# untitled.net
KiCad netlist of a schematic drawn in EAGLE
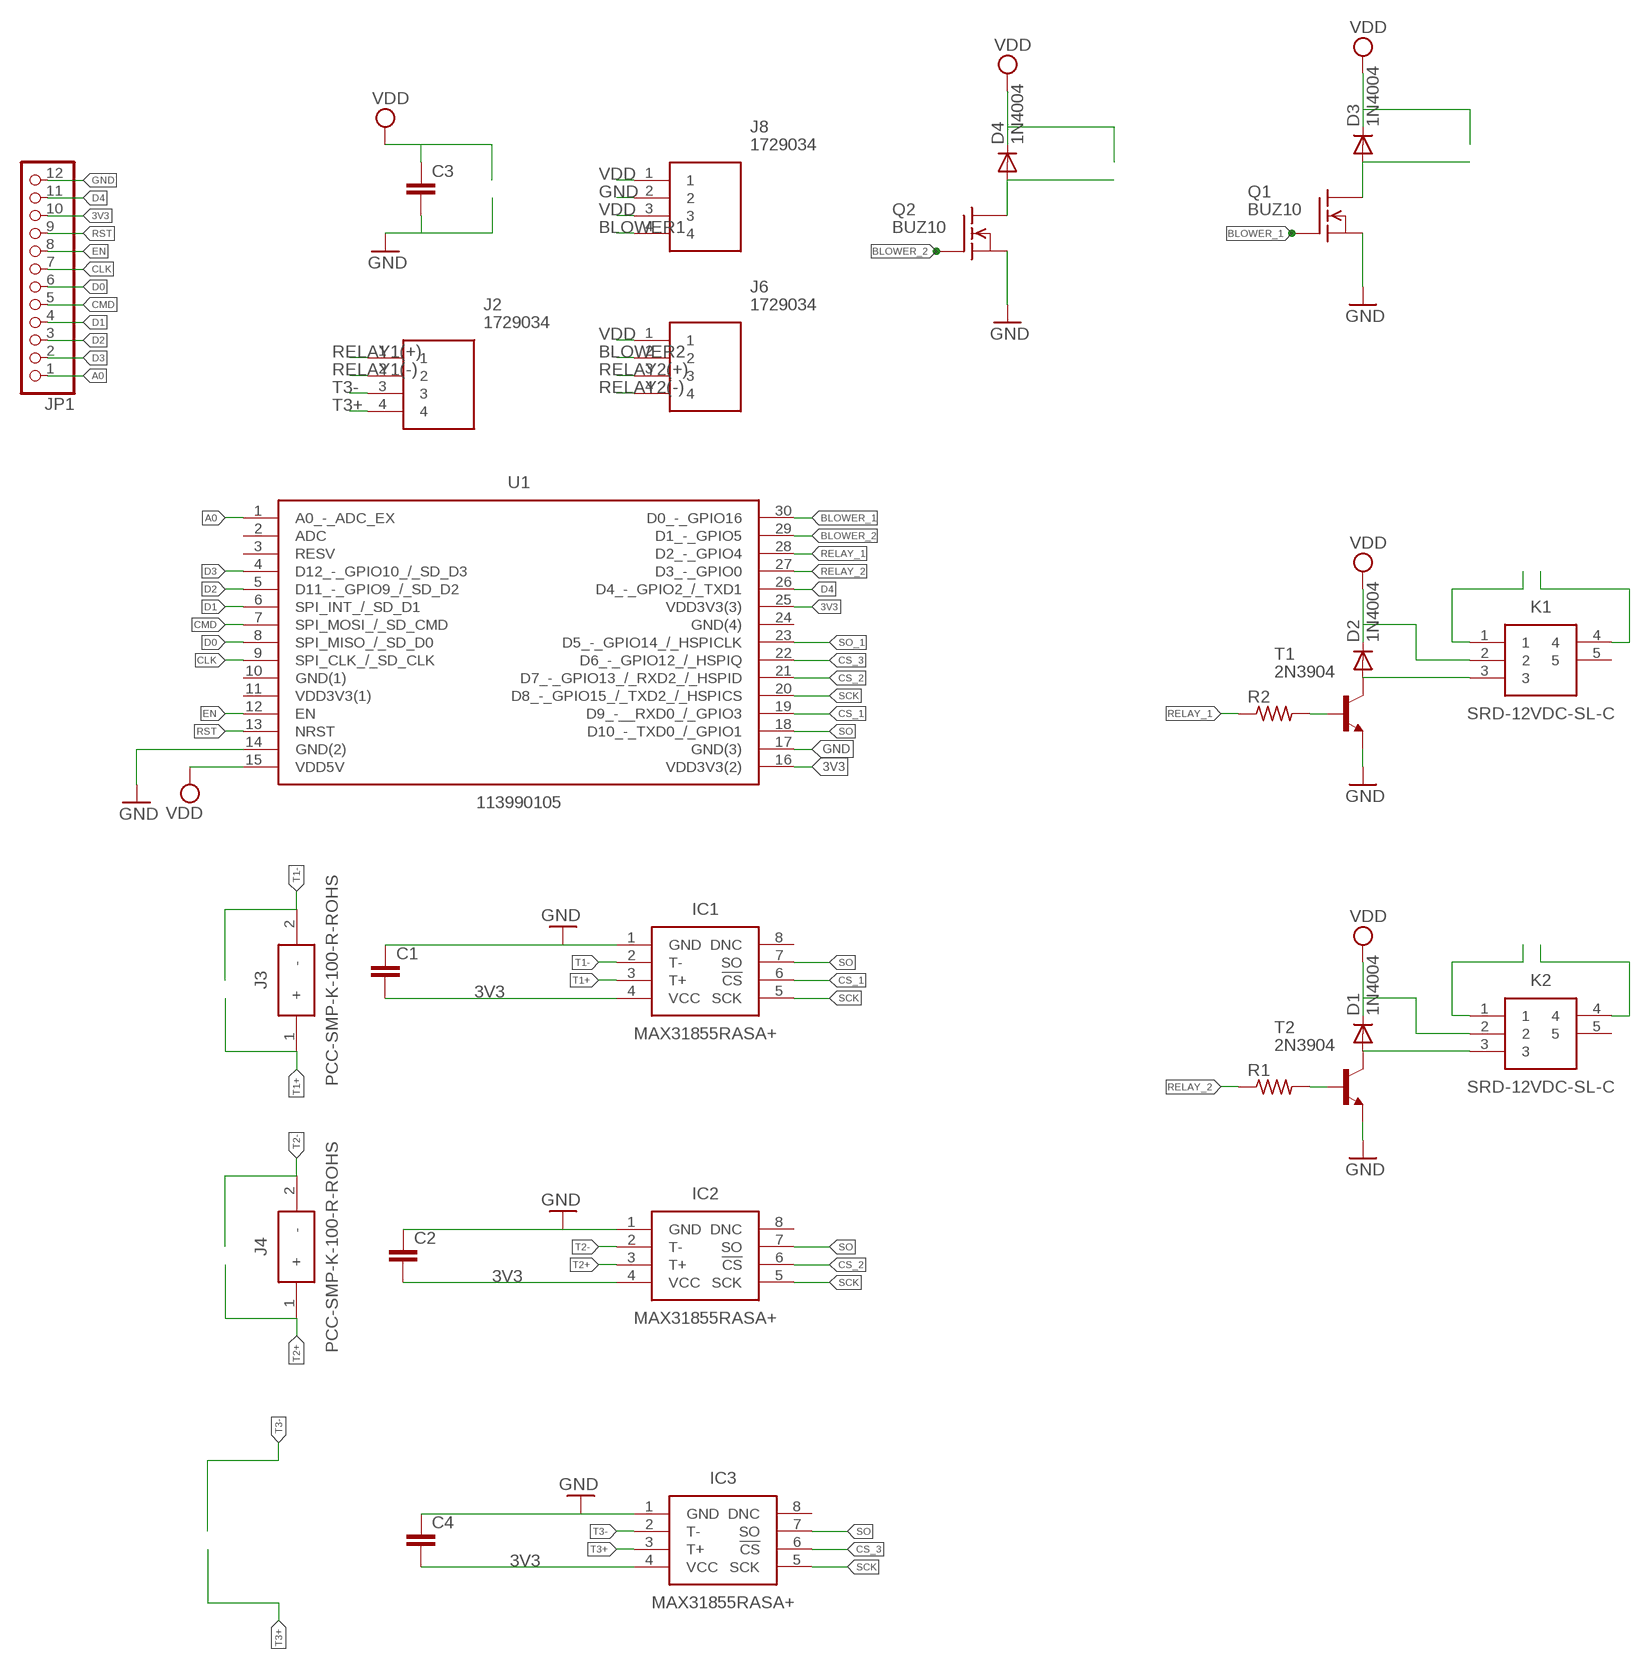
[diagram p0: schematic, sheet 1]

(export (version "E")
  (design (tool "Eeschema 10.0.6"))
  (components
    (comp (ref "C1")
      (value "C2,5-3")
      (footprint "eagle-import:C2.5-3")
      (libsource (lib "eagle-import") (part "C2,5-3"))
    )
    (comp (ref "C2")
      (value "C2,5-3")
      (footprint "eagle-import:C2.5-3")
      (libsource (lib "eagle-import") (part "C2,5-3"))
    )
    (comp (ref "C3")
      (value "C2.5/4")
      (footprint "eagle-import:C2.5-4")
      (libsource (lib "eagle-import") (part "C2.5/4"))
    )
    (comp (ref "C4")
      (value "C2,5-3")
      (footprint "eagle-import:C2.5-3")
      (libsource (lib "eagle-import") (part "C2,5-3"))
    )
    (comp (ref "D1")
      (value "1N4004")
      (footprint "eagle-import:DO41-10")
      (libsource (lib "eagle-import") (part "1N4004"))
    )
    (comp (ref "D2")
      (value "1N4004")
      (footprint "eagle-import:DO41-10")
      (libsource (lib "eagle-import") (part "1N4004"))
    )
    (comp (ref "D3")
      (value "1N4004")
      (footprint "eagle-import:DO41-10")
      (libsource (lib "eagle-import") (part "1N4004"))
    )
    (comp (ref "D4")
      (value "1N4004")
      (footprint "eagle-import:DO41-10")
      (libsource (lib "eagle-import") (part "1N4004"))
    )
    (comp (ref "IC1")
      (value "MAX31855RASA+")
      (footprint "eagle-import:SOIC127P600X175-8N")
      (fields (field (name "RS_PART_NUMBER") "7833891P"))
      (libsource (lib "eagle-import") (part "MAX31855RASA+"))
    )
    (comp (ref "IC2")
      (value "MAX31855RASA+")
      (footprint "eagle-import:SOIC127P600X175-8N")
      (fields (field (name "RS_PART_NUMBER") "7833891P"))
      (libsource (lib "eagle-import") (part "MAX31855RASA+"))
    )
    (comp (ref "IC3")
      (value "MAX31855RASA+")
      (footprint "eagle-import:SOIC127P600X175-8N")
      (fields (field (name "RS_PART_NUMBER") "7833891P"))
      (libsource (lib "eagle-import") (part "MAX31855RASA+"))
    )
    (comp (ref "J2")
      (value "1729034")
      (footprint "eagle-import:SHDR4W110P0X500_1X4_2000X810X1")
      (fields (field (name "RS_PART_NUMBER") "8020620"))
      (libsource (lib "eagle-import") (part "1729034"))
    )
    (comp (ref "J3")
      (value "PCC-SMP-K-100-R-ROHS")
      (footprint "eagle-import:PCC-SMP")
      (libsource (lib "eagle-import") (part "PCC-SMP-K-100-R-ROHS"))
    )
    (comp (ref "J4")
      (value "PCC-SMP-K-100-R-ROHS")
      (footprint "eagle-import:PCC-SMP")
      (libsource (lib "eagle-import") (part "PCC-SMP-K-100-R-ROHS"))
    )
    (comp (ref "J6")
      (value "1729034")
      (footprint "eagle-import:SHDR4W110P0X500_1X4_2000X810X1")
      (fields (field (name "RS_PART_NUMBER") "8020620"))
      (libsource (lib "eagle-import") (part "1729034"))
    )
    (comp (ref "J8")
      (value "1729034")
      (footprint "eagle-import:SHDR4W110P0X500_1X4_2000X810X1")
      (fields (field (name "RS_PART_NUMBER") "8020620"))
      (libsource (lib "eagle-import") (part "1729034"))
    )
    (comp (ref "JP1")
      (value "PINHD-1X12")
      (footprint "eagle-import:1X12")
      (libsource (lib "eagle-import") (part "PINHD-1X12"))
    )
    (comp (ref "K1")
      (value "SRD-12VDC-SL-C")
      (footprint "eagle-import:SRD")
      (libsource (lib "eagle-import") (part "SRD-12VDC-SL-C"))
    )
    (comp (ref "K2")
      (value "SRD-12VDC-SL-C")
      (footprint "eagle-import:SRD")
      (libsource (lib "eagle-import") (part "SRD-12VDC-SL-C"))
    )
    (comp (ref "Q1")
      (value "BUZ10")
      (footprint "eagle-import:TO220")
      (libsource (lib "eagle-import") (part "BUZ10"))
    )
    (comp (ref "Q2")
      (value "BUZ10")
      (footprint "eagle-import:TO220")
      (libsource (lib "eagle-import") (part "BUZ10"))
    )
    (comp (ref "R1")
      (value "R-US_0207/7")
      (footprint "eagle-import:0207_7")
      (libsource (lib "eagle-import") (part "R-US_0207/7"))
    )
    (comp (ref "R2")
      (value "R-US_0207/7")
      (footprint "eagle-import:0207_7")
      (libsource (lib "eagle-import") (part "R-US_0207/7"))
    )
    (comp (ref "T1")
      (value "2N3904")
      (footprint "eagle-import:TO92")
      (libsource (lib "eagle-import") (part "2N3904"))
    )
    (comp (ref "T2")
      (value "2N3904")
      (footprint "eagle-import:TO92")
      (libsource (lib "eagle-import") (part "2N3904"))
    )
    (comp (ref "U1")
      (value "113990105")
      (footprint "eagle-import:DIP2286W64P254L4826H735Q30N")
      (libsource (lib "eagle-import") (part "113990105"))
    )
  )
  (nets
    (net (code "1") (name "/BLOWER1") (class "Default")
      (node (ref "D3") (pin "A") (pinfunction "A_A") (pintype "passive"))
      (node (ref "J8") (pin "4") (pinfunction "4_4") (pintype "bidirectional"))
      (node (ref "Q1") (pin "2") (pinfunction "D_2") (pintype "passive"))
    )
    (net (code "2") (name "/BLOWER2") (class "Default")
      (node (ref "D4") (pin "A") (pinfunction "A_A") (pintype "passive"))
      (node (ref "J6") (pin "2") (pinfunction "2_2") (pintype "bidirectional"))
      (node (ref "Q2") (pin "2") (pinfunction "D_2") (pintype "passive"))
    )
    (net (code "3") (name "/GND(1)") (class "Default")
      (node (ref "U1") (pin "10") (pinfunction "GND(1)_10") (pintype "power_in"))
    )
    (net (code "4") (name "/GND(4)") (class "Default")
      (node (ref "U1") (pin "24") (pinfunction "GND(4)_24") (pintype "power_in"))
    )
    (net (code "5") (name "/RELAY1(+)") (class "Default")
      (node (ref "J2") (pin "1") (pinfunction "1_1") (pintype "bidirectional"))
      (node (ref "K1") (pin "4") (pinfunction "4_4") (pintype "passive"))
    )
    (net (code "6") (name "/RELAY1(-)") (class "Default")
      (node (ref "J2") (pin "2") (pinfunction "2_2") (pintype "bidirectional"))
      (node (ref "K1") (pin "1") (pinfunction "1_1") (pintype "passive"))
    )
    (net (code "7") (name "/RELAY2(+)") (class "Default")
      (node (ref "J6") (pin "3") (pinfunction "3_3") (pintype "bidirectional"))
      (node (ref "K2") (pin "4") (pinfunction "4_4") (pintype "passive"))
    )
    (net (code "8") (name "/RELAY2(-)") (class "Default")
      (node (ref "J6") (pin "4") (pinfunction "4_4") (pintype "bidirectional"))
      (node (ref "K2") (pin "1") (pinfunction "1_1") (pintype "passive"))
    )
    (net (code "9") (name "/VDD3V3(1)") (class "Default")
      (node (ref "U1") (pin "11") (pinfunction "VDD3V3(1)_11") (pintype "power_in"))
    )
    (net (code "10") (name "3V3") (class "Default")
      (node (ref "C1") (pin "2") (pinfunction "2_2") (pintype "passive"))
      (node (ref "C2") (pin "2") (pinfunction "2_2") (pintype "passive"))
      (node (ref "C4") (pin "2") (pinfunction "2_2") (pintype "passive"))
      (node (ref "IC1") (pin "4") (pinfunction "VCC_4") (pintype "power_in"))
      (node (ref "IC2") (pin "4") (pinfunction "VCC_4") (pintype "power_in"))
      (node (ref "IC3") (pin "4") (pinfunction "VCC_4") (pintype "power_in"))
      (node (ref "JP1") (pin "10") (pinfunction "10_10") (pintype "passive"))
      (node (ref "U1") (pin "16") (pinfunction "VDD3V3(2)_16") (pintype "power_in"))
      (node (ref "U1") (pin "25") (pinfunction "VDD3V3(3)_25") (pintype "power_in"))
    )
    (net (code "11") (name "A0") (class "Default")
      (node (ref "JP1") (pin "1") (pinfunction "1_1") (pintype "passive"))
      (node (ref "U1") (pin "1") (pinfunction "A0_-_ADC_EX_1") (pintype "bidirectional"))
    )
    (net (code "12") (name "BLOWER_1") (class "Default")
      (node (ref "Q1") (pin "1") (pinfunction "G_1") (pintype "passive"))
      (node (ref "U1") (pin "30") (pinfunction "D0_-_GPIO16_30") (pintype "bidirectional"))
    )
    (net (code "13") (name "BLOWER_2") (class "Default")
      (node (ref "Q2") (pin "1") (pinfunction "G_1") (pintype "passive"))
      (node (ref "U1") (pin "29") (pinfunction "D1_-_GPIO5_29") (pintype "bidirectional"))
    )
    (net (code "14") (name "CLK") (class "Default")
      (node (ref "JP1") (pin "7") (pinfunction "7_7") (pintype "passive"))
      (node (ref "U1") (pin "9") (pinfunction "SPI_CLK_/_SD_CLK_9") (pintype "bidirectional"))
    )
    (net (code "15") (name "CMD") (class "Default")
      (node (ref "JP1") (pin "5") (pinfunction "5_5") (pintype "passive"))
      (node (ref "U1") (pin "7") (pinfunction "SPI_MOSI_/_SD_CMD_7") (pintype "bidirectional"))
    )
    (net (code "16") (name "CS_1") (class "Default")
      (node (ref "IC1") (pin "6") (pinfunction "~{CS}_6") (pintype "input"))
      (node (ref "U1") (pin "19") (pinfunction "D9_-__RXD0_/_GPIO3_19") (pintype "bidirectional"))
    )
    (net (code "17") (name "CS_2") (class "Default")
      (node (ref "IC2") (pin "6") (pinfunction "~{CS}_6") (pintype "input"))
      (node (ref "U1") (pin "21") (pinfunction "D7_-_GPIO13_/_RXD2_/_HSPID_21") (pintype "bidirectional"))
    )
    (net (code "18") (name "CS_3") (class "Default")
      (node (ref "IC3") (pin "6") (pinfunction "~{CS}_6") (pintype "input"))
      (node (ref "U1") (pin "22") (pinfunction "D6_-_GPIO12_/_HSPIQ_22") (pintype "bidirectional"))
    )
    (net (code "19") (name "D0") (class "Default")
      (node (ref "JP1") (pin "6") (pinfunction "6_6") (pintype "passive"))
      (node (ref "U1") (pin "8") (pinfunction "SPI_MISO_/_SD_D0_8") (pintype "bidirectional"))
    )
    (net (code "20") (name "D1") (class "Default")
      (node (ref "JP1") (pin "4") (pinfunction "4_4") (pintype "passive"))
      (node (ref "U1") (pin "6") (pinfunction "SPI_INT_/_SD_D1_6") (pintype "bidirectional"))
    )
    (net (code "21") (name "D2") (class "Default")
      (node (ref "JP1") (pin "3") (pinfunction "3_3") (pintype "passive"))
      (node (ref "U1") (pin "5") (pinfunction "D11_-_GPIO9_/_SD_D2_5") (pintype "bidirectional"))
    )
    (net (code "22") (name "D3") (class "Default")
      (node (ref "JP1") (pin "2") (pinfunction "2_2") (pintype "passive"))
      (node (ref "U1") (pin "4") (pinfunction "D12_-_GPIO10_/_SD_D3_4") (pintype "bidirectional"))
    )
    (net (code "23") (name "D4") (class "Default")
      (node (ref "JP1") (pin "11") (pinfunction "11_11") (pintype "passive"))
      (node (ref "U1") (pin "26") (pinfunction "D4_-_GPIO2_/_TXD1_26") (pintype "bidirectional"))
    )
    (net (code "24") (name "EN") (class "Default")
      (node (ref "JP1") (pin "8") (pinfunction "8_8") (pintype "passive"))
      (node (ref "U1") (pin "12") (pinfunction "EN_12") (pintype "input"))
    )
    (net (code "25") (name "GND") (class "Default")
      (node (ref "C1") (pin "1") (pinfunction "1_1") (pintype "passive"))
      (node (ref "C2") (pin "1") (pinfunction "1_1") (pintype "passive"))
      (node (ref "C3") (pin "2") (pinfunction "2_2") (pintype "passive"))
      (node (ref "C4") (pin "1") (pinfunction "1_1") (pintype "passive"))
      (node (ref "IC1") (pin "1") (pinfunction "GND_1") (pintype "power_in"))
      (node (ref "IC2") (pin "1") (pinfunction "GND_1") (pintype "power_in"))
      (node (ref "IC3") (pin "1") (pinfunction "GND_1") (pintype "power_in"))
      (node (ref "J8") (pin "2") (pinfunction "2_2") (pintype "bidirectional"))
      (node (ref "JP1") (pin "12") (pinfunction "12_12") (pintype "passive"))
      (node (ref "Q1") (pin "3") (pinfunction "S_3") (pintype "passive"))
      (node (ref "Q2") (pin "3") (pinfunction "S_3") (pintype "passive"))
      (node (ref "T1") (pin "3") (pinfunction "E_3") (pintype "passive"))
      (node (ref "T2") (pin "3") (pinfunction "E_3") (pintype "passive"))
      (node (ref "U1") (pin "14") (pinfunction "GND(2)_14") (pintype "power_in"))
      (node (ref "U1") (pin "17") (pinfunction "GND(3)_17") (pintype "power_in"))
    )
    (net (code "26") (name "Net-(T1-B)") (class "Default")
      (node (ref "R2") (pin "2") (pinfunction "2_2") (pintype "passive"))
      (node (ref "T1") (pin "2") (pinfunction "B_2") (pintype "passive"))
    )
    (net (code "27") (name "Net-(T1-C)") (class "Default")
      (node (ref "D2") (pin "A") (pinfunction "A_A") (pintype "passive"))
      (node (ref "K1") (pin "3") (pinfunction "3_3") (pintype "passive"))
      (node (ref "T1") (pin "1") (pinfunction "C_1") (pintype "passive"))
    )
    (net (code "28") (name "Net-(T2-B)") (class "Default")
      (node (ref "R1") (pin "2") (pinfunction "2_2") (pintype "passive"))
      (node (ref "T2") (pin "2") (pinfunction "B_2") (pintype "passive"))
    )
    (net (code "29") (name "Net-(T2-C)") (class "Default")
      (node (ref "D1") (pin "A") (pinfunction "A_A") (pintype "passive"))
      (node (ref "K2") (pin "3") (pinfunction "3_3") (pintype "passive"))
      (node (ref "T2") (pin "1") (pinfunction "C_1") (pintype "passive"))
    )
    (net (code "30") (name "RELAY_1") (class "Default")
      (node (ref "R2") (pin "1") (pinfunction "1_1") (pintype "passive"))
      (node (ref "U1") (pin "28") (pinfunction "D2_-_GPIO4_28") (pintype "bidirectional"))
    )
    (net (code "31") (name "RELAY_2") (class "Default")
      (node (ref "R1") (pin "1") (pinfunction "1_1") (pintype "passive"))
      (node (ref "U1") (pin "27") (pinfunction "D3_-_GPIO0_27") (pintype "bidirectional"))
    )
    (net (code "32") (name "RST") (class "Default")
      (node (ref "JP1") (pin "9") (pinfunction "9_9") (pintype "passive"))
      (node (ref "U1") (pin "13") (pinfunction "NRST_13") (pintype "input"))
    )
    (net (code "33") (name "SCK") (class "Default")
      (node (ref "IC1") (pin "5") (pinfunction "SCK_5") (pintype "input"))
      (node (ref "IC2") (pin "5") (pinfunction "SCK_5") (pintype "input"))
      (node (ref "IC3") (pin "5") (pinfunction "SCK_5") (pintype "input"))
      (node (ref "U1") (pin "20") (pinfunction "D8_-_GPIO15_/_TXD2_/_HSPICS_20") (pintype "bidirectional"))
    )
    (net (code "34") (name "SO") (class "Default")
      (node (ref "IC1") (pin "7") (pinfunction "SO_7") (pintype "output"))
      (node (ref "IC2") (pin "7") (pinfunction "SO_7") (pintype "output"))
      (node (ref "IC3") (pin "7") (pinfunction "SO_7") (pintype "output"))
      (node (ref "U1") (pin "18") (pinfunction "D10_-_TXD0_/_GPIO1_18") (pintype "bidirectional"))
    )
    (net (code "35") (name "SO_1") (class "Default")
      (node (ref "U1") (pin "23") (pinfunction "D5_-_GPIO14_/_HSPICLK_23") (pintype "bidirectional"))
    )
    (net (code "36") (name "T1+") (class "Default")
      (node (ref "IC1") (pin "3") (pinfunction "T+_3") (pintype "input"))
      (node (ref "J3") (pin "1") (pinfunction "+_1") (pintype "passive"))
    )
    (net (code "37") (name "T1-") (class "Default")
      (node (ref "IC1") (pin "2") (pinfunction "T-_2") (pintype "input"))
      (node (ref "J3") (pin "2") (pinfunction "-_2") (pintype "passive"))
    )
    (net (code "38") (name "T2+") (class "Default")
      (node (ref "IC2") (pin "3") (pinfunction "T+_3") (pintype "input"))
      (node (ref "J4") (pin "1") (pinfunction "+_1") (pintype "passive"))
    )
    (net (code "39") (name "T2-") (class "Default")
      (node (ref "IC2") (pin "2") (pinfunction "T-_2") (pintype "input"))
      (node (ref "J4") (pin "2") (pinfunction "-_2") (pintype "passive"))
    )
    (net (code "40") (name "T3+") (class "Default")
      (node (ref "IC3") (pin "3") (pinfunction "T+_3") (pintype "input"))
      (node (ref "J2") (pin "4") (pinfunction "4_4") (pintype "bidirectional"))
    )
    (net (code "41") (name "T3-") (class "Default")
      (node (ref "IC3") (pin "2") (pinfunction "T-_2") (pintype "input"))
      (node (ref "J2") (pin "3") (pinfunction "3_3") (pintype "bidirectional"))
    )
    (net (code "42") (name "VDD") (class "Default")
      (node (ref "C3") (pin "1") (pinfunction "1_1") (pintype "passive"))
      (node (ref "D1") (pin "C") (pinfunction "C_C") (pintype "passive"))
      (node (ref "D2") (pin "C") (pinfunction "C_C") (pintype "passive"))
      (node (ref "D3") (pin "C") (pinfunction "C_C") (pintype "passive"))
      (node (ref "D4") (pin "C") (pinfunction "C_C") (pintype "passive"))
      (node (ref "J6") (pin "1") (pinfunction "1_1") (pintype "bidirectional"))
      (node (ref "J8") (pin "1") (pinfunction "1_1") (pintype "bidirectional"))
      (node (ref "J8") (pin "3") (pinfunction "3_3") (pintype "bidirectional"))
      (node (ref "K1") (pin "2") (pinfunction "2_2") (pintype "passive"))
      (node (ref "K2") (pin "2") (pinfunction "2_2") (pintype "passive"))
      (node (ref "U1") (pin "15") (pinfunction "VDD5V_15") (pintype "power_in"))
    )
    (net (code "43") (name "unconnected-(IC1-DNC-Pad8)") (class "Default")
      (node (ref "IC1") (pin "8") (pinfunction "DNC_8") (pintype "passive"))
    )
    (net (code "44") (name "unconnected-(IC2-DNC-Pad8)") (class "Default")
      (node (ref "IC2") (pin "8") (pinfunction "DNC_8") (pintype "passive"))
    )
    (net (code "45") (name "unconnected-(IC3-DNC-Pad8)") (class "Default")
      (node (ref "IC3") (pin "8") (pinfunction "DNC_8") (pintype "passive"))
    )
    (net (code "46") (name "unconnected-(K1-Pad5)") (class "Default")
      (node (ref "K1") (pin "5") (pinfunction "5_5") (pintype "passive"))
    )
    (net (code "47") (name "unconnected-(K2-Pad5)") (class "Default")
      (node (ref "K2") (pin "5") (pinfunction "5_5") (pintype "passive"))
    )
    (net (code "48") (name "unconnected-(U1-ADC-Pad2)") (class "Default")
      (node (ref "U1") (pin "2") (pinfunction "ADC_2") (pintype "bidirectional"))
    )
    (net (code "49") (name "unconnected-(U1-RESV-Pad3)") (class "Default")
      (node (ref "U1") (pin "3") (pinfunction "RESV_3") (pintype "passive"))
    )
  )
)
